# PCB-IO-PROTECTION-INDUCTANCE-1.net
KiCad netlist of a schematic drawn in Altium Designer
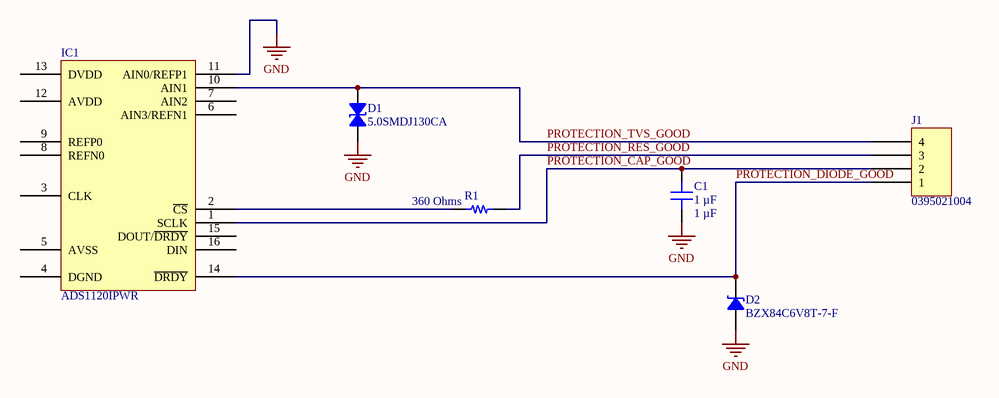
[diagram p0: PCB-IO-PROTECTION-INDUCTANCE-1.SchDoc]

(export (version "E")
  (design (tool "Eeschema 10.0.6"))
  (components
    (comp (ref "C1")
      (value "1 µF")
      (footprint "CAP 0603_1608")
      (description "CAP CER 1UF 16V X7R 0603")
      (fields (field (name "PART NUMBER") "C0603C105K4RACAUTO") (field (name "ALTIUM_VALUE") "1 µF"))
      (libsource (lib "Celestial Altium Library - altium_library") (part "Capacitor"))
    )
    (comp (ref "D1")
      (value "5.0SMDJ130CA")
      (footprint "DO214AB SMC")
      (description "TVS DIODE 130VWM 209VC DO214AB")
      (libsource (lib "Celestial Altium Library - altium_library") (part "Diode TVS"))
    )
    (comp (ref "D2")
      (value "BZX84C6V8T-7-F")
      (footprint "DIODES SOT-523")
      (description "DIODE ZENER 6.8V 150MW SOT523")
      (libsource (lib "Celestial Altium Library - altium_library") (part "Diode Zener"))
    )
    (comp (ref "IC1")
      (value "ADS1120IPWR")
      (footprint "TI TSSOP-16 PW")
      (description "IC ADC 16BIT SIGMA-DELTA 16TSSOP")
      (libsource (lib "Celestial Altium Library - altium_library") (part "TI ADS1120 TSSOP"))
    )
    (comp (ref "J1")
      (value "0395021004")
      (footprint "MOLEX 395021004")
      (description "TERM BLOCK HDR 4POS 90DEG 3.5MM")
      (fields (field (name "MANUFACTURER") "Molex"))
      (libsource (lib "Celestial Altium Library - altium_library") (part "4 Pin"))
    )
    (comp (ref "R1")
      (value "360 Ohms")
      (footprint "RES 0603_1608")
      (description "RES SMD 360 OHM 0.1% 1/5W 0603")
      (fields (field (name "PART NUMBER") "ERJ-PB3B3600V"))
      (libsource (lib "Celestial Altium Library - altium_library") (part "Resistor"))
    )
  )
  (nets
    (net (code "1") (name "/PROTECTION_CAP_GOOD") (class "Default")
      (node (ref "C1") (pin "2") (pinfunction "2_2") (pintype "passive"))
      (node (ref "IC1") (pin "1") (pinfunction "SCLK_1") (pintype "passive"))
      (node (ref "J1") (pin "2") (pinfunction "2_2") (pintype "passive"))
    )
    (net (code "2") (name "/PROTECTION_DIODE_GOOD") (class "Default")
      (node (ref "D2") (pin "2") (pinfunction "2_2") (pintype "passive"))
      (node (ref "IC1") (pin "14") (pinfunction "~{DRDY}_14") (pintype "passive"))
      (node (ref "J1") (pin "1") (pinfunction "1_1") (pintype "passive"))
    )
    (net (code "3") (name "/PROTECTION_RES_GOOD") (class "Default")
      (node (ref "J1") (pin "3") (pinfunction "3_3") (pintype "passive"))
      (node (ref "R1") (pin "2") (pinfunction "2_2") (pintype "passive"))
    )
    (net (code "4") (name "/PROTECTION_TVS_GOOD") (class "Default")
      (node (ref "D1") (pin "2") (pinfunction "2_2") (pintype "passive"))
      (node (ref "IC1") (pin "10") (pinfunction "AIN1_10") (pintype "passive"))
      (node (ref "J1") (pin "4") (pinfunction "4_4") (pintype "passive"))
    )
    (net (code "5") (name "GND") (class "Default")
      (node (ref "C1") (pin "1") (pinfunction "1_1") (pintype "passive"))
      (node (ref "D1") (pin "1") (pinfunction "1_1") (pintype "passive"))
      (node (ref "D2") (pin "1") (pinfunction "1_1") (pintype "passive"))
      (node (ref "IC1") (pin "11") (pinfunction "AIN0/REFP1_11") (pintype "passive"))
    )
    (net (code "6") (name "Net-(IC1-~{CS})") (class "Default")
      (node (ref "IC1") (pin "2") (pinfunction "~{CS}_2") (pintype "passive"))
      (node (ref "R1") (pin "1") (pinfunction "1_1") (pintype "passive"))
    )
    (net (code "7") (name "unconnected-(IC1-AIN2-Pad7)") (class "Default")
      (node (ref "IC1") (pin "7") (pinfunction "AIN2_7") (pintype "passive"))
    )
    (net (code "8") (name "unconnected-(IC1-AIN3{slash}REFN1-Pad6)") (class "Default")
      (node (ref "IC1") (pin "6") (pinfunction "AIN3/REFN1_6") (pintype "passive"))
    )
    (net (code "9") (name "unconnected-(IC1-AVDD-Pad12)") (class "Default")
      (node (ref "IC1") (pin "12") (pinfunction "AVDD_12") (pintype "passive"))
    )
    (net (code "10") (name "unconnected-(IC1-AVSS-Pad5)") (class "Default")
      (node (ref "IC1") (pin "5") (pinfunction "AVSS_5") (pintype "passive"))
    )
    (net (code "11") (name "unconnected-(IC1-CLK-Pad3)") (class "Default")
      (node (ref "IC1") (pin "3") (pinfunction "CLK_3") (pintype "passive"))
    )
    (net (code "12") (name "unconnected-(IC1-DGND-Pad4)") (class "Default")
      (node (ref "IC1") (pin "4") (pinfunction "DGND_4") (pintype "passive"))
    )
    (net (code "13") (name "unconnected-(IC1-DIN-Pad16)") (class "Default")
      (node (ref "IC1") (pin "16") (pinfunction "DIN_16") (pintype "passive"))
    )
    (net (code "14") (name "unconnected-(IC1-DOUT{slash}~{DRDY}-Pad15)") (class "Default")
      (node (ref "IC1") (pin "15") (pinfunction "DOUT/~{DRDY}_15") (pintype "passive"))
    )
    (net (code "15") (name "unconnected-(IC1-DVDD-Pad13)") (class "Default")
      (node (ref "IC1") (pin "13") (pinfunction "DVDD_13") (pintype "passive"))
    )
    (net (code "16") (name "unconnected-(IC1-REFN0-Pad8)") (class "Default")
      (node (ref "IC1") (pin "8") (pinfunction "REFN0_8") (pintype "passive"))
    )
    (net (code "17") (name "unconnected-(IC1-REFP0-Pad9)") (class "Default")
      (node (ref "IC1") (pin "9") (pinfunction "REFP0_9") (pintype "passive"))
    )
  )
)
